# USB2PPM.net
KiCad netlist of a schematic drawn in EAGLE
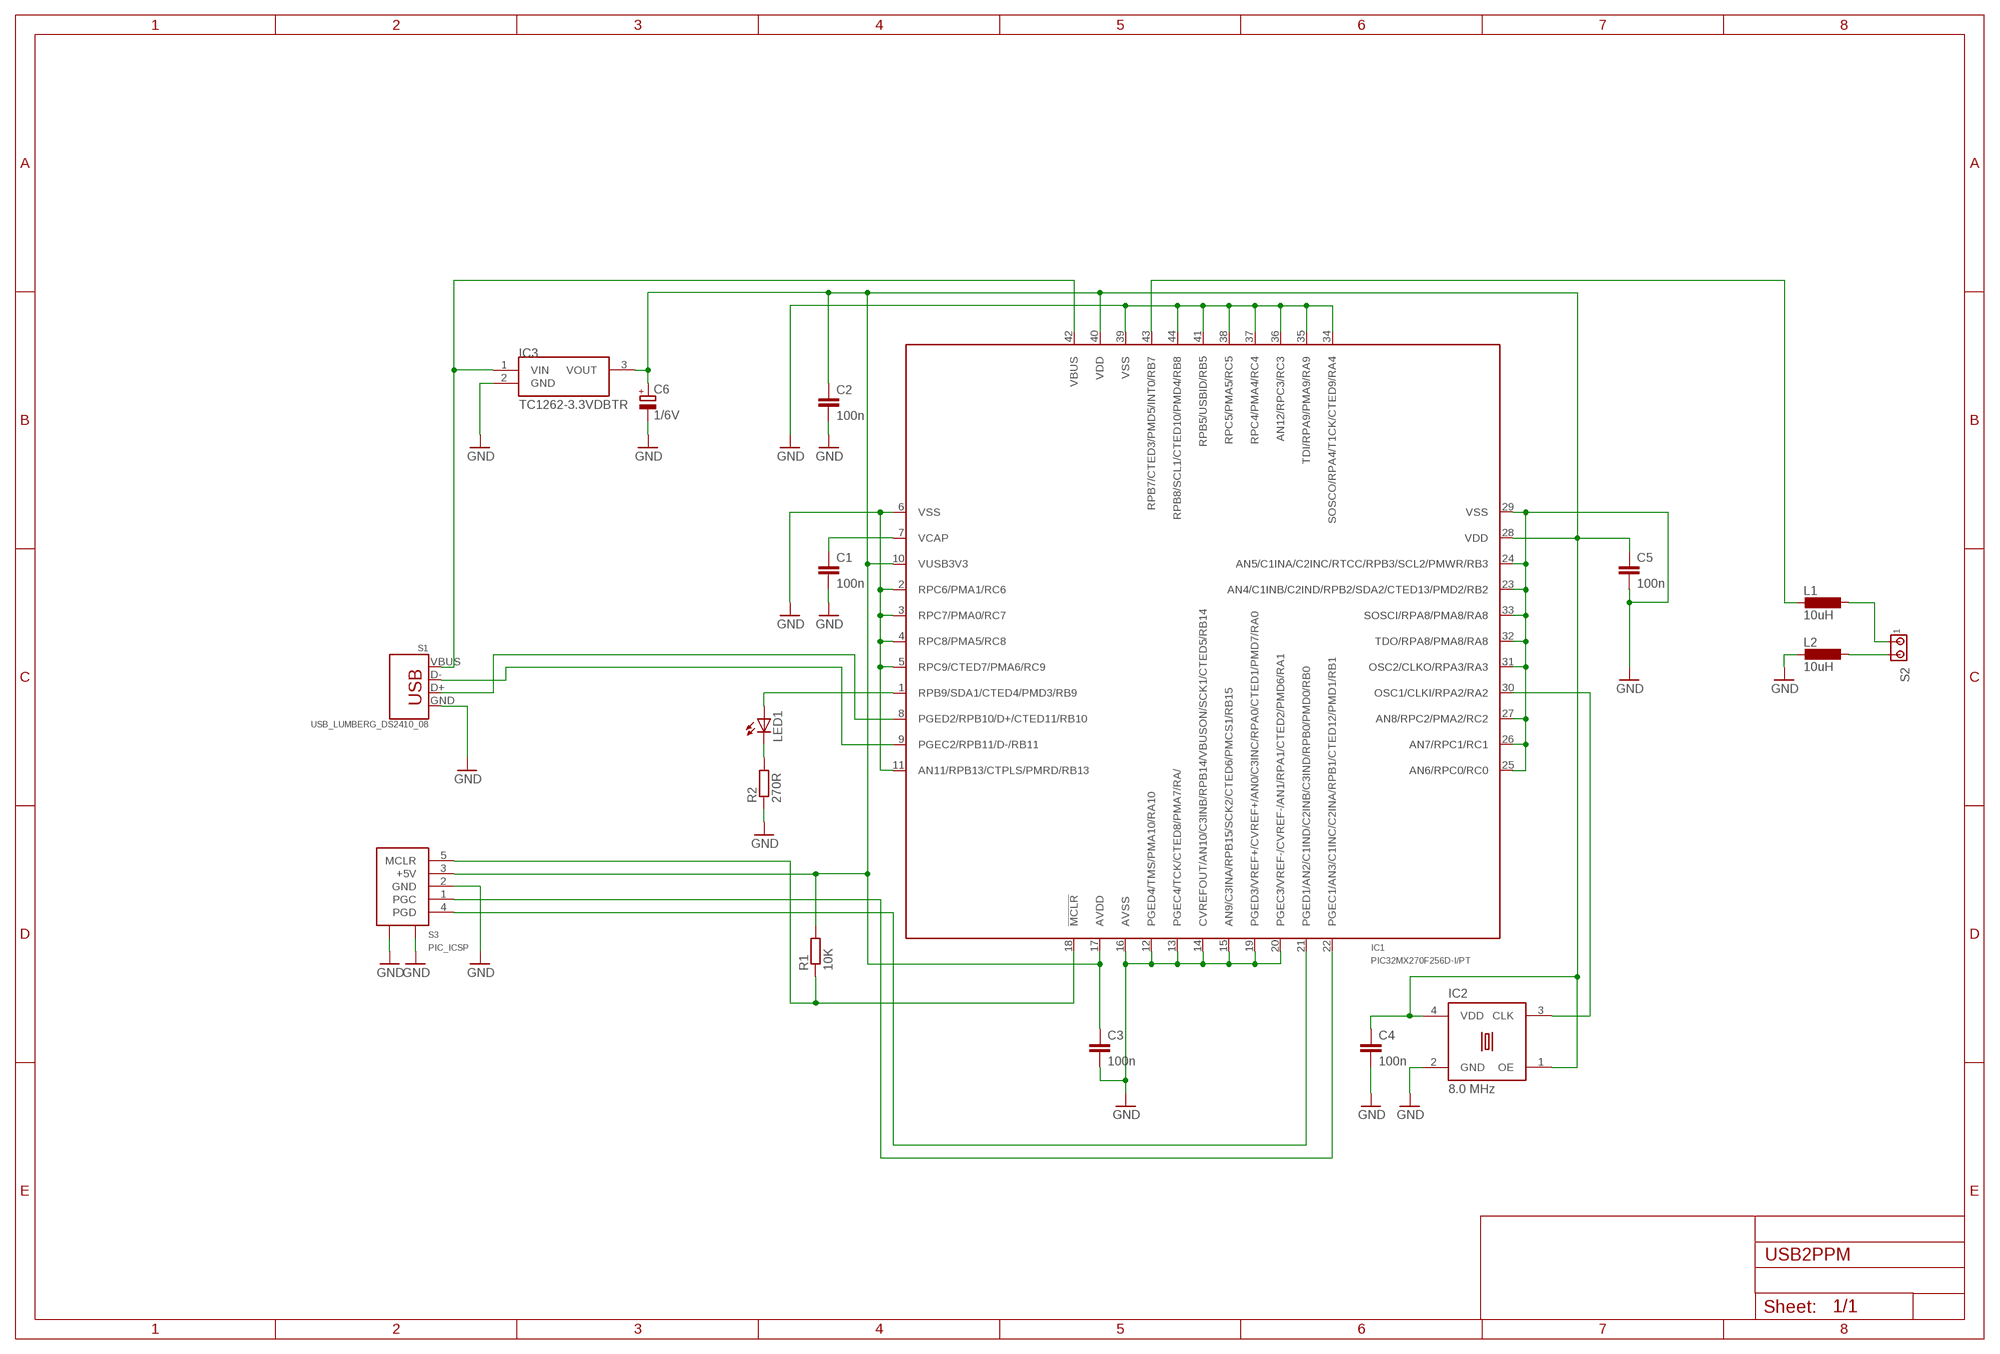
[diagram p0: schematic, sheet 1]

(export (version "E")
  (design (tool "Eeschema 10.0.6"))
  (components
    (comp (ref "C1")
      (value "100n")
      (footprint "eagle-import:C0805K")
      (libsource (lib "eagle-import") (part "C-EUC0805K"))
    )
    (comp (ref "C2")
      (value "100n")
      (footprint "eagle-import:C0805K")
      (libsource (lib "eagle-import") (part "C-EUC0805K"))
    )
    (comp (ref "C3")
      (value "100n")
      (footprint "eagle-import:C0805K")
      (libsource (lib "eagle-import") (part "C-EUC0805K"))
    )
    (comp (ref "C4")
      (value "100n")
      (footprint "eagle-import:C0805K")
      (libsource (lib "eagle-import") (part "C-EUC0805K"))
    )
    (comp (ref "C5")
      (value "100n")
      (footprint "eagle-import:C0805K")
      (libsource (lib "eagle-import") (part "C-EUC0805K"))
    )
    (comp (ref "C6")
      (value "1/6V")
      (footprint "eagle-import:SMC_A")
      (libsource (lib "eagle-import") (part "CPOL-EUSMCA"))
    )
    (comp (ref "IC1")
      (value "PIC32MX270F256D-I/PT")
      (footprint "eagle-import:TQFP44")
      (libsource (lib "eagle-import") (part "PIC32MX250F128D-I/PT"))
    )
    (comp (ref "IC2")
      (value "8.0 MHz")
      (footprint "eagle-import:DFN_3.2X5MM(4MM)")
      (libsource (lib "eagle-import") (part "501_SI3.2X4"))
    )
    (comp (ref "IC3")
      (value "TC1262-3.3VDBTR")
      (footprint "eagle-import:SOT223")
      (libsource (lib "eagle-import") (part "MCP1703"))
    )
    (comp (ref "L1")
      (value "10uH")
      (footprint "eagle-import:L3225M")
      (libsource (lib "eagle-import") (part "L-EUL3225M"))
    )
    (comp (ref "L2")
      (value "10uH")
      (footprint "eagle-import:L3225M")
      (libsource (lib "eagle-import") (part "L-EUL3225M"))
    )
    (comp (ref "LED1")
      (value "LEDSML0805")
      (footprint "eagle-import:SML0805")
      (libsource (lib "eagle-import") (part "LEDSML0805"))
    )
    (comp (ref "R1")
      (value "10K")
      (footprint "eagle-import:R0805W")
      (libsource (lib "eagle-import") (part "R-EU_R0805W"))
    )
    (comp (ref "R2")
      (value "270R")
      (footprint "eagle-import:R0805W")
      (libsource (lib "eagle-import") (part "R-EU_R0805W"))
    )
    (comp (ref "S1")
      (value "USB_LUMBERG_DS2410_08")
      (footprint "eagle-import:USB-A-LUMBERG_DS2410_08")
      (libsource (lib "eagle-import") (part "USB_LUMBERG_DS2410_08"))
    )
    (comp (ref "S2")
      (value "MTA02-100")
      (footprint "eagle-import:10X02MTA")
      (libsource (lib "eagle-import") (part "MTA02-100"))
    )
    (comp (ref "S3")
      (value "PIC_ICSP")
      (footprint "eagle-import:53395-05_GND")
      (libsource (lib "eagle-import") (part "PIC_ICSP"))
    )
  )
  (nets
    (net (code "1") (name "GND") (class "Default")
      (node (ref "C1") (pin "2") (pinfunction "2_2") (pintype "passive"))
      (node (ref "C2") (pin "2") (pinfunction "2_2") (pintype "passive"))
      (node (ref "C3") (pin "2") (pinfunction "2_2") (pintype "passive"))
      (node (ref "C4") (pin "2") (pinfunction "2_2") (pintype "passive"))
      (node (ref "C5") (pin "2") (pinfunction "2_2") (pintype "passive"))
      (node (ref "C6") (pin "-") (pinfunction "-_-") (pintype "passive"))
      (node (ref "IC1") (pin "11") (pinfunction "AN11/RPB13/CTPLS/PMRD/RB13_11") (pintype "bidirectional"))
      (node (ref "IC1") (pin "12") (pinfunction "PGED4/TMS/PMA10/RA10_12") (pintype "input"))
      (node (ref "IC1") (pin "13") (pinfunction "PGEC4/TCK/CTED8/PMA7/RA/_13") (pintype "input"))
      (node (ref "IC1") (pin "14") (pinfunction "CVREFOUT/AN10/C3INB/RPB14/VBUSON/SCK1/CTED5/RB14_14") (pintype "bidirectional"))
      (node (ref "IC1") (pin "15") (pinfunction "AN9/C3INA/RPB15/SCK2/CTED6/PMCS1/RB15_15") (pintype "bidirectional"))
      (node (ref "IC1") (pin "16") (pinfunction "AVSS_16") (pintype "power_in"))
      (node (ref "IC1") (pin "19") (pinfunction "PGED3/VREF+/CVREF+/AN0/C3INC/RPA0/CTED1/PMD7/RA0_19") (pintype "bidirectional"))
      (node (ref "IC1") (pin "2") (pinfunction "RPC6/PMA1/RC6_2") (pintype "bidirectional"))
      (node (ref "IC1") (pin "20") (pinfunction "PGEC3/VREF-/CVREF-/AN1/RPA1/CTED2/PMD6/RA1_20") (pintype "bidirectional"))
      (node (ref "IC1") (pin "23") (pinfunction "AN4/C1INB/C2IND/RPB2/SDA2/CTED13/PMD2/RB2_23") (pintype "bidirectional"))
      (node (ref "IC1") (pin "24") (pinfunction "AN5/C1INA/C2INC/RTCC/RPB3/SCL2/PMWR/RB3_24") (pintype "bidirectional"))
      (node (ref "IC1") (pin "25") (pinfunction "AN6/RPC0/RC0_25") (pintype "bidirectional"))
      (node (ref "IC1") (pin "26") (pinfunction "AN7/RPC1/RC1_26") (pintype "bidirectional"))
      (node (ref "IC1") (pin "27") (pinfunction "AN8/RPC2/PMA2/RC2_27") (pintype "bidirectional"))
      (node (ref "IC1") (pin "29") (pinfunction "VSS_29") (pintype "power_in"))
      (node (ref "IC1") (pin "3") (pinfunction "RPC7/PMA0/RC7_3") (pintype "bidirectional"))
      (node (ref "IC1") (pin "31") (pinfunction "OSC2/CLKO/RPA3/RA3_31") (pintype "bidirectional"))
      (node (ref "IC1") (pin "32") (pinfunction "TDO/RPA8/PMA8/RA8_32") (pintype "output"))
      (node (ref "IC1") (pin "33") (pinfunction "SOSCI/RPA8/PMA8/RA8_33") (pintype "bidirectional"))
      (node (ref "IC1") (pin "34") (pinfunction "SOSCO/RPA4/T1CK/CTED9/RA4_34") (pintype "bidirectional"))
      (node (ref "IC1") (pin "35") (pinfunction "TDI/RPA9/PMA9/RA9_35") (pintype "input"))
      (node (ref "IC1") (pin "36") (pinfunction "AN12/RPC3/RC3_36") (pintype "bidirectional"))
      (node (ref "IC1") (pin "37") (pinfunction "RPC4/PMA4/RC4_37") (pintype "bidirectional"))
      (node (ref "IC1") (pin "38") (pinfunction "RPC5/PMA5/RC5_38") (pintype "bidirectional"))
      (node (ref "IC1") (pin "39") (pinfunction "VSS_39") (pintype "power_in"))
      (node (ref "IC1") (pin "4") (pinfunction "RPC8/PMA5/RC8_4") (pintype "bidirectional"))
      (node (ref "IC1") (pin "41") (pinfunction "RPB5/USBID/RB5_41") (pintype "bidirectional"))
      (node (ref "IC1") (pin "44") (pinfunction "RPB8/SCL1/CTED10/PMD4/RB8_44") (pintype "bidirectional"))
      (node (ref "IC1") (pin "5") (pinfunction "RPC9/CTED7/PMA6/RC9_5") (pintype "bidirectional"))
      (node (ref "IC1") (pin "6") (pinfunction "VSS_6") (pintype "power_in"))
      (node (ref "IC2") (pin "2") (pinfunction "GND_2") (pintype "power_in"))
      (node (ref "IC3") (pin "2") (pinfunction "GND_2") (pintype "bidirectional"))
      (node (ref "L2") (pin "2") (pinfunction "2_2") (pintype "passive"))
      (node (ref "R2") (pin "1") (pinfunction "1_1") (pintype "passive"))
      (node (ref "S1") (pin "GND") (pinfunction "VBUS_GND") (pintype "power_in"))
      (node (ref "S3") (pin "2") (pinfunction "GND_2") (pintype "bidirectional"))
      (node (ref "S3") (pin "S1") (pinfunction "GND_S1") (pintype "power_in"))
      (node (ref "S3") (pin "S2") (pinfunction "GND_S2") (pintype "power_in"))
    )
    (net (code "2") (name "Net-(IC1-AVDD)") (class "Default")
      (node (ref "C2") (pin "1") (pinfunction "1_1") (pintype "passive"))
      (node (ref "C3") (pin "1") (pinfunction "1_1") (pintype "passive"))
      (node (ref "C4") (pin "1") (pinfunction "1_1") (pintype "passive"))
      (node (ref "C5") (pin "1") (pinfunction "1_1") (pintype "passive"))
      (node (ref "C6") (pin "+") (pinfunction "+_+") (pintype "passive"))
      (node (ref "IC1") (pin "10") (pinfunction "VUSB3V3_10") (pintype "passive"))
      (node (ref "IC1") (pin "17") (pinfunction "AVDD_17") (pintype "power_in"))
      (node (ref "IC1") (pin "28") (pinfunction "VDD_28") (pintype "power_in"))
      (node (ref "IC1") (pin "40") (pinfunction "VDD_40") (pintype "power_in"))
      (node (ref "IC2") (pin "1") (pinfunction "OE_1") (pintype "input"))
      (node (ref "IC2") (pin "4") (pinfunction "VDD_4") (pintype "power_in"))
      (node (ref "IC3") (pin "3") (pinfunction "VOUT_3") (pintype "bidirectional"))
      (node (ref "R1") (pin "2") (pinfunction "2_2") (pintype "passive"))
      (node (ref "S3") (pin "3") (pinfunction "+5V_3") (pintype "bidirectional"))
    )
    (net (code "3") (name "Net-(IC1-OSC1{slash}CLKI{slash}RPA2{slash}RA2)") (class "Default")
      (node (ref "IC1") (pin "30") (pinfunction "OSC1/CLKI/RPA2/RA2_30") (pintype "bidirectional"))
      (node (ref "IC2") (pin "3") (pinfunction "CLK_3") (pintype "output"))
    )
    (net (code "4") (name "Net-(IC1-PGEC1{slash}AN3{slash}C1INC{slash}C2INA{slash}RPB1{slash}CTED12{slash}PMD1{slash}RB1)") (class "Default")
      (node (ref "IC1") (pin "22") (pinfunction "PGEC1/AN3/C1INC/C2INA/RPB1/CTED12/PMD1/RB1_22") (pintype "bidirectional"))
      (node (ref "S3") (pin "1") (pinfunction "PGC_1") (pintype "bidirectional"))
    )
    (net (code "5") (name "Net-(IC1-PGEC2{slash}RPB11{slash}D-{slash}RB11)") (class "Default")
      (node (ref "IC1") (pin "9") (pinfunction "PGEC2/RPB11/D-/RB11_9") (pintype "bidirectional"))
      (node (ref "S1") (pin "D-") (pinfunction "D+_D-") (pintype "bidirectional"))
    )
    (net (code "6") (name "Net-(IC1-PGED1{slash}AN2{slash}C1IND{slash}C2INB{slash}C3IND{slash}RPB0{slash}PMD0{slash}RB0)") (class "Default")
      (node (ref "IC1") (pin "21") (pinfunction "PGED1/AN2/C1IND/C2INB/C3IND/RPB0/PMD0/RB0_21") (pintype "bidirectional"))
      (node (ref "S3") (pin "4") (pinfunction "PGD_4") (pintype "bidirectional"))
    )
    (net (code "7") (name "Net-(IC1-PGED2{slash}RPB10{slash}D+{slash}CTED11{slash}RB10)") (class "Default")
      (node (ref "IC1") (pin "8") (pinfunction "PGED2/RPB10/D+/CTED11/RB10_8") (pintype "bidirectional"))
      (node (ref "S1") (pin "D+") (pinfunction "D-_D+") (pintype "bidirectional"))
    )
    (net (code "8") (name "Net-(IC1-RPB7{slash}CTED3{slash}PMD5{slash}INT0{slash}RB7)") (class "Default")
      (node (ref "IC1") (pin "43") (pinfunction "RPB7/CTED3/PMD5/INT0/RB7_43") (pintype "bidirectional"))
      (node (ref "L1") (pin "2") (pinfunction "2_2") (pintype "passive"))
    )
    (net (code "9") (name "Net-(IC1-RPB9{slash}SDA1{slash}CTED4{slash}PMD3{slash}RB9)") (class "Default")
      (node (ref "IC1") (pin "1") (pinfunction "RPB9/SDA1/CTED4/PMD3/RB9_1") (pintype "bidirectional"))
      (node (ref "LED1") (pin "A") (pinfunction "A_A") (pintype "passive"))
    )
    (net (code "10") (name "Net-(IC1-VBUS)") (class "Default")
      (node (ref "IC1") (pin "42") (pinfunction "VBUS_42") (pintype "passive"))
      (node (ref "IC3") (pin "1") (pinfunction "VIN_1") (pintype "bidirectional"))
      (node (ref "S1") (pin "VBUS") (pinfunction "GND_VBUS") (pintype "power_in"))
    )
    (net (code "11") (name "Net-(IC1-VCAP)") (class "Default")
      (node (ref "C1") (pin "1") (pinfunction "1_1") (pintype "passive"))
      (node (ref "IC1") (pin "7") (pinfunction "VCAP_7") (pintype "bidirectional"))
    )
    (net (code "12") (name "Net-(IC1-~{MCLR})") (class "Default")
      (node (ref "IC1") (pin "18") (pinfunction "~{MCLR}_18") (pintype "input"))
      (node (ref "R1") (pin "1") (pinfunction "1_1") (pintype "passive"))
      (node (ref "S3") (pin "5") (pinfunction "MCLR_5") (pintype "bidirectional"))
    )
    (net (code "13") (name "Net-(L1-Pad1)") (class "Default")
      (node (ref "L1") (pin "1") (pinfunction "1_1") (pintype "passive"))
      (node (ref "S2") (pin "1") (pinfunction "1_1") (pintype "passive"))
    )
    (net (code "14") (name "Net-(L2-Pad1)") (class "Default")
      (node (ref "L2") (pin "1") (pinfunction "1_1") (pintype "passive"))
      (node (ref "S2") (pin "2") (pinfunction "2_2") (pintype "passive"))
    )
    (net (code "15") (name "Net-(LED1-PadC)") (class "Default")
      (node (ref "LED1") (pin "C") (pinfunction "C_C") (pintype "passive"))
      (node (ref "R2") (pin "2") (pinfunction "2_2") (pintype "passive"))
    )
  )
)
